# 5V-to-12V-Converter-ManyDiodes.net
KiCad netlist of a schematic drawn in EAGLE
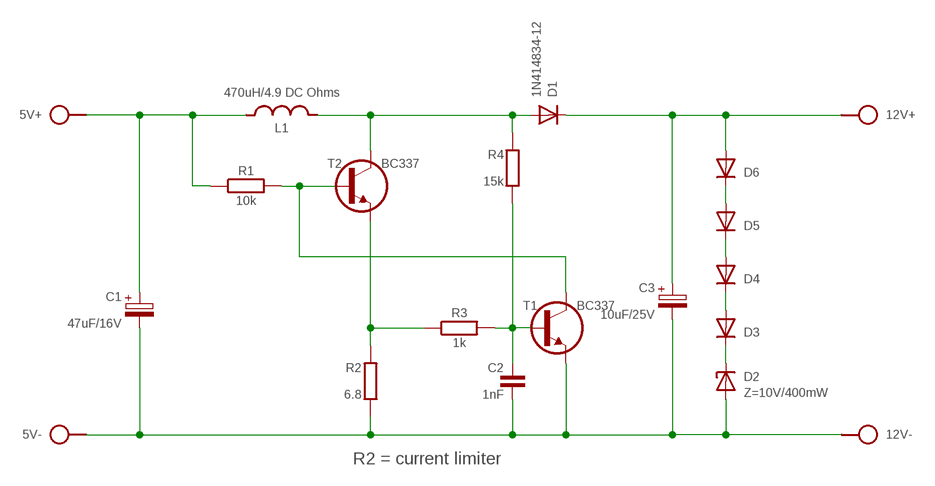
[diagram p0: schematic, sheet 1]

(export (version "E")
  (design (tool "Eeschema 10.0.6"))
  (components
    (comp (ref "5V")
      (value "SPAD+--+")
      (footprint "eagle-import:SPAD-+")
      (libsource (lib "eagle-import") (part "SPAD+--+"))
    )
    (comp (ref "12V")
      (value "SPAD+-+-")
      (footprint "eagle-import:SPAD+-")
      (libsource (lib "eagle-import") (part "SPAD+-+-"))
    )
    (comp (ref "C1")
      (value "47uF/16V")
      (footprint "eagle-import:E2.5-4_V")
      (libsource (lib "eagle-import") (part "CPOLE2,5-4/V"))
    )
    (comp (ref "C2")
      (value "1nF")
      (footprint "eagle-import:C050-020X036")
      (libsource (lib "eagle-import") (part "C050-020X036"))
    )
    (comp (ref "C3")
      (value "10uF/25V")
      (footprint "eagle-import:E2.5-4_V")
      (libsource (lib "eagle-import") (part "CPOLE2,5-4/V"))
    )
    (comp (ref "D1")
      (value "1N414834-12")
      (footprint "eagle-import:DO34-12")
      (libsource (lib "eagle-import") (part "1N414834-12"))
    )
    (comp (ref "D2")
      (value "Z=10V/400mW")
      (footprint "eagle-import:DO35Z10_V")
      (libsource (lib "eagle-import") (part "Z-DIODE-35Z10/V"))
    )
    (comp (ref "D3")
      (value "1N4002-2.54A")
      (footprint "eagle-import:DO35-2_54A")
      (libsource (lib "eagle-import") (part "1N4002-2.54A"))
    )
    (comp (ref "D4")
      (value "1N4002-2.54")
      (footprint "eagle-import:DO35-2_54")
      (libsource (lib "eagle-import") (part "1N4002-2.54"))
    )
    (comp (ref "D5")
      (value "1N4002-2.54A")
      (footprint "eagle-import:DO35-2_54A")
      (libsource (lib "eagle-import") (part "1N4002-2.54A"))
    )
    (comp (ref "D6")
      (value "1N4002-2.54")
      (footprint "eagle-import:DO35-2_54")
      (libsource (lib "eagle-import") (part "1N4002-2.54"))
    )
    (comp (ref "L1")
      (value "470uH/4.9 DC Ohms")
      (footprint "eagle-import:ED16-X")
      (libsource (lib "eagle-import") (part "L-SHORTED16-X"))
    )
    (comp (ref "R1")
      (value "10k")
      (footprint "eagle-import:0204_7-V")
      (libsource (lib "eagle-import") (part "R-H0204/7-V"))
    )
    (comp (ref "R2")
      (value "6.8")
      (footprint "eagle-import:0204_10")
      (libsource (lib "eagle-import") (part "R0204/10"))
    )
    (comp (ref "R3")
      (value "1k")
      (footprint "eagle-import:0204_10")
      (libsource (lib "eagle-import") (part "R-H0204/10"))
    )
    (comp (ref "R4")
      (value "15k")
      (footprint "eagle-import:0204_7-V")
      (libsource (lib "eagle-import") (part "R0204/7-V"))
    )
    (comp (ref "T1")
      (value "BC337")
      (footprint "eagle-import:TO92-CBE")
      (libsource (lib "eagle-import") (part "BC337CBE"))
    )
    (comp (ref "T2")
      (value "BC337")
      (footprint "eagle-import:TO92-CBE")
      (libsource (lib "eagle-import") (part "BC337CBE"))
    )
  )
  (nets
    (net (code "1") (name "Net-(5VA-P$1)") (class "Default")
      (node (ref "5V") (pin "2") (pinfunction "P$1_2") (pintype "passive"))
      (node (ref "C1") (pin "+") (pinfunction "+_+") (pintype "passive"))
      (node (ref "L1") (pin "1") (pinfunction "1_1") (pintype "passive"))
      (node (ref "R1") (pin "1") (pinfunction "1_1") (pintype "passive"))
    )
    (net (code "2") (name "Net-(12VA-P$1)") (class "Default")
      (node (ref "12V") (pin "2") (pinfunction "P$1_2") (pintype "passive"))
      (node (ref "C3") (pin "+") (pinfunction "+_+") (pintype "passive"))
      (node (ref "D1") (pin "C") (pinfunction "C_C") (pintype "passive"))
      (node (ref "D6") (pin "A") (pinfunction "A_A") (pintype "passive"))
    )
    (net (code "3") (name "Net-(12VB-P$1)") (class "Default")
      (node (ref "12V") (pin "1") (pinfunction "P$1_1") (pintype "passive"))
      (node (ref "5V") (pin "1") (pinfunction "P$1_1") (pintype "passive"))
      (node (ref "C1") (pin "-") (pinfunction "-_-") (pintype "passive"))
      (node (ref "C2") (pin "2") (pinfunction "2_2") (pintype "passive"))
      (node (ref "C3") (pin "-") (pinfunction "-_-") (pintype "passive"))
      (node (ref "D2") (pin "A") (pinfunction "A_A") (pintype "passive"))
      (node (ref "R2") (pin "1") (pinfunction "2_1") (pintype "passive"))
      (node (ref "T1") (pin "E") (pinfunction "E_E") (pintype "passive"))
    )
    (net (code "4") (name "Net-(D2-PadC)") (class "Default")
      (node (ref "D2") (pin "C") (pinfunction "C_C") (pintype "passive"))
      (node (ref "D3") (pin "C") (pinfunction "C_C") (pintype "passive"))
    )
    (net (code "5") (name "Net-(D3-PadA)") (class "Default")
      (node (ref "D3") (pin "A") (pinfunction "A_A") (pintype "passive"))
      (node (ref "D4") (pin "C") (pinfunction "C_C") (pintype "passive"))
    )
    (net (code "6") (name "Net-(D4-PadA)") (class "Default")
      (node (ref "D4") (pin "A") (pinfunction "A_A") (pintype "passive"))
      (node (ref "D5") (pin "C") (pinfunction "C_C") (pintype "passive"))
    )
    (net (code "7") (name "Net-(D5-PadA)") (class "Default")
      (node (ref "D5") (pin "A") (pinfunction "A_A") (pintype "passive"))
      (node (ref "D6") (pin "C") (pinfunction "C_C") (pintype "passive"))
    )
    (net (code "8") (name "Net-(R1-Pad2)") (class "Default")
      (node (ref "R1") (pin "2") (pinfunction "2_2") (pintype "passive"))
      (node (ref "T1") (pin "C") (pinfunction "C_C") (pintype "passive"))
      (node (ref "T2") (pin "B") (pinfunction "B_B") (pintype "passive"))
    )
    (net (code "9") (name "Net-(R2-1)") (class "Default")
      (node (ref "R2") (pin "2") (pinfunction "1_2") (pintype "passive"))
      (node (ref "R3") (pin "1") (pinfunction "1_1") (pintype "passive"))
      (node (ref "T2") (pin "E") (pinfunction "E_E") (pintype "passive"))
    )
    (net (code "10") (name "Net-(R4-1)") (class "Default")
      (node (ref "D1") (pin "A") (pinfunction "A_A") (pintype "passive"))
      (node (ref "L1") (pin "2") (pinfunction "2_2") (pintype "passive"))
      (node (ref "R4") (pin "2") (pinfunction "1_2") (pintype "passive"))
      (node (ref "T2") (pin "C") (pinfunction "C_C") (pintype "passive"))
    )
    (net (code "11") (name "Net-(R4-2)") (class "Default")
      (node (ref "C2") (pin "1") (pinfunction "1_1") (pintype "passive"))
      (node (ref "R3") (pin "2") (pinfunction "2_2") (pintype "passive"))
      (node (ref "R4") (pin "1") (pinfunction "2_1") (pintype "passive"))
      (node (ref "T1") (pin "B") (pinfunction "B_B") (pintype "passive"))
    )
  )
)
